# BBB_Connections.net
KiCad netlist of a schematic drawn in Altium Designer
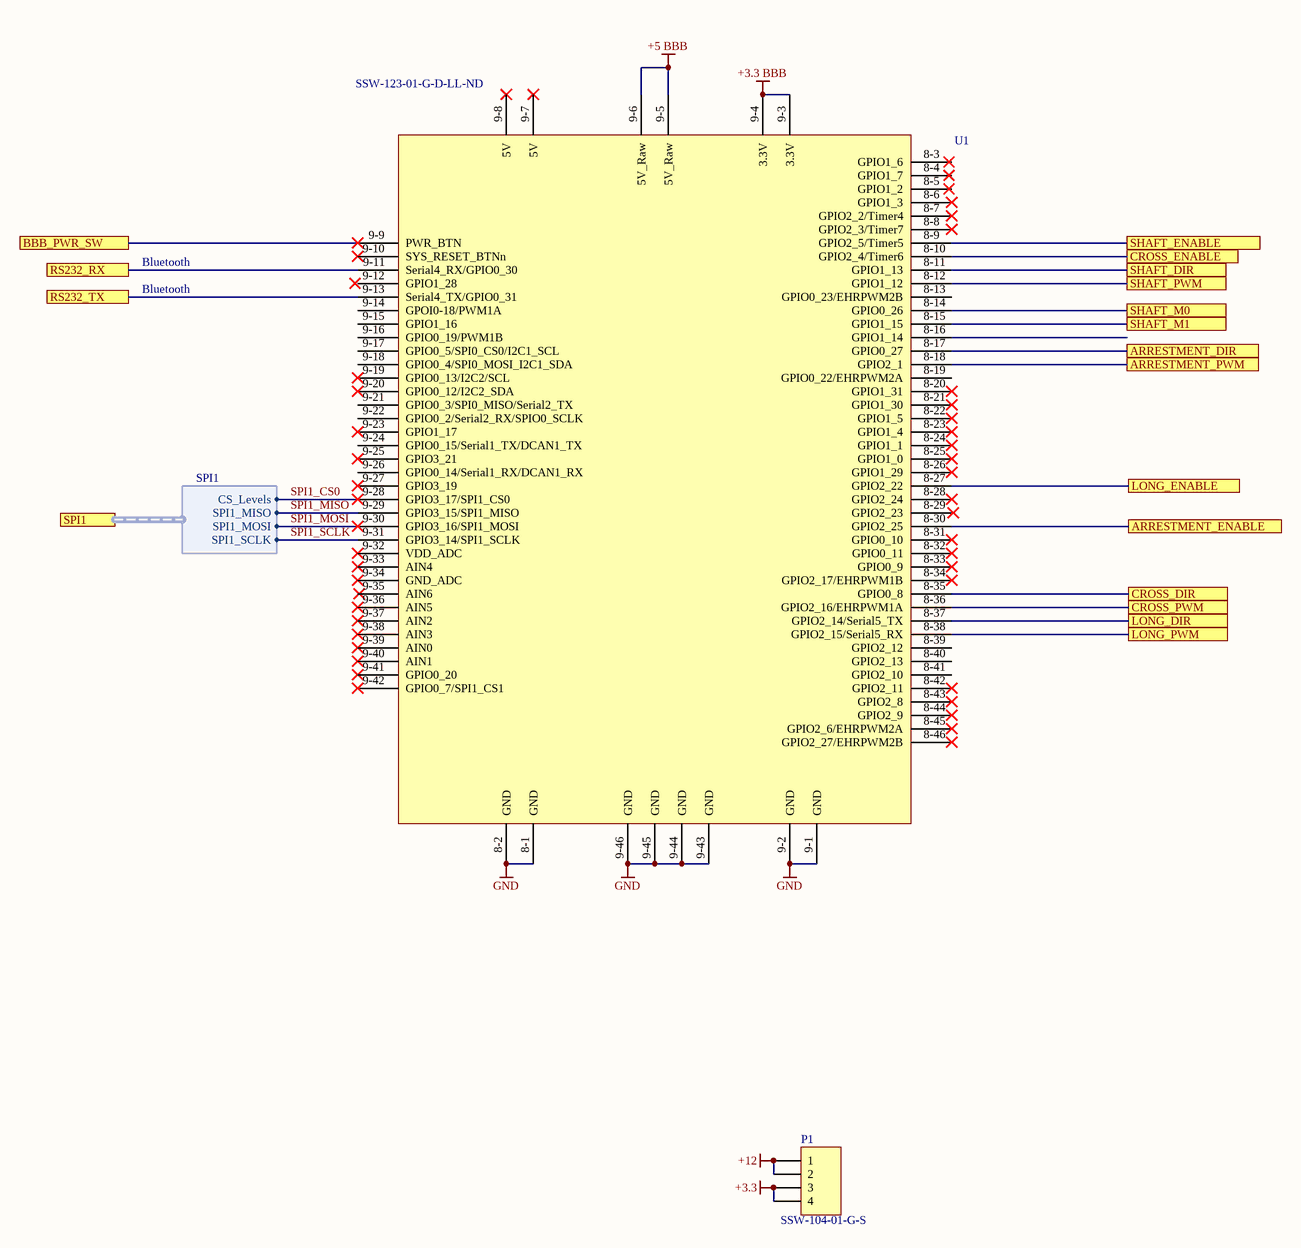
[diagram p0: BBB_Connections.SchDoc]

(export (version "E")
  (design (tool "Eeschema 10.0.6"))
  (components
    (comp (ref "P1")
      (value "SSW-104-01-G-S")
      (footprint "HDR1X4")
      (description "Header, 4-Pin")
      (fields (field (name "MANUFACTURER") "Samtec Inc."))
      (libsource (lib "Miscellaneous Connectors") (part "Header 4"))
    )
    (comp (ref "U1")
      (value "BBB")
      (footprint "Beaglebone Black Mezanine")
      (description "Beaglebone Black")
      (fields
        (field (name "SUPPLIER PART NUMBER 1") "SSW-123-01-G-D-LL-ND")
        (field (name "MANUFACTURER") "Samtec Inc.")
        (field (name "MANUFACTURER PART NUMBER") "SSW-123-01-G-D-LL")
      )
      (libsource (lib "ZLS_Schematic_lib") (part "Beaglebone_Black_Mezanine"))
    )
  )
  (nets
    (net (code "2") (name "+3.3") (class "Default")
      (node (ref "P1") (pin "3") (pinfunction "3_3") (pintype "passive"))
      (node (ref "P1") (pin "4") (pinfunction "4_4") (pintype "passive"))
    )
    (net (code "3") (name "+3.3 BBB") (class "Default")
      (node (ref "U1") (pin "9-3") (pinfunction "3.3V_9-3") (pintype "passive"))
      (node (ref "U1") (pin "9-4") (pinfunction "3.3V_9-4") (pintype "passive"))
    )
    (net (code "4") (name "+5 BBB") (class "Default")
      (node (ref "U1") (pin "9-5") (pinfunction "5V_Raw_9-5") (pintype "passive"))
      (node (ref "U1") (pin "9-6") (pinfunction "5V_Raw_9-6") (pintype "passive"))
    )
    (net (code "5") (name "+12") (class "Default")
      (node (ref "P1") (pin "1") (pinfunction "1_1") (pintype "passive"))
      (node (ref "P1") (pin "2") (pinfunction "2_2") (pintype "passive"))
    )
    (net (code "6") (name "/ARRESTMENT_DIR") (class "Default")
      (node (ref "U1") (pin "8-17") (pinfunction "GPIO0_27_8-17") (pintype "passive"))
    )
    (net (code "7") (name "/ARRESTMENT_ENABLE") (class "Default")
      (node (ref "U1") (pin "8-30") (pinfunction "GPIO2_25_8-30") (pintype "passive"))
    )
    (net (code "8") (name "/ARRESTMENT_PWM") (class "Default")
      (node (ref "U1") (pin "8-18") (pinfunction "GPIO2_1_8-18") (pintype "passive"))
    )
    (net (code "9") (name "/BBB_PWR_SW") (class "Default")
      (node (ref "U1") (pin "9-9") (pinfunction "PWR_BTN_9-9") (pintype "passive+no_connect"))
    )
    (net (code "10") (name "/CROSS_DIR") (class "Default")
      (node (ref "U1") (pin "8-35") (pinfunction "GPIO0_8_8-35") (pintype "passive"))
    )
    (net (code "11") (name "/CROSS_ENABLE") (class "Default")
      (node (ref "U1") (pin "8-10") (pinfunction "GPIO2_4/Timer6_8-10") (pintype "passive"))
    )
    (net (code "12") (name "/CROSS_PWM") (class "Default")
      (node (ref "U1") (pin "8-36") (pinfunction "GPIO2_16/EHRPWM1A_8-36") (pintype "passive"))
    )
    (net (code "13") (name "/LONG_DIR") (class "Default")
      (node (ref "U1") (pin "8-37") (pinfunction "GPIO2_14/Serial5_TX_8-37") (pintype "passive"))
    )
    (net (code "14") (name "/LONG_ENABLE") (class "Default")
      (node (ref "U1") (pin "8-27") (pinfunction "GPIO2_22_8-27") (pintype "passive"))
    )
    (net (code "15") (name "/LONG_PWM") (class "Default")
      (node (ref "U1") (pin "8-38") (pinfunction "GPIO2_15/Serial5_RX_8-38") (pintype "passive"))
    )
    (net (code "16") (name "/RS232_RX") (class "Default")
      (node (ref "U1") (pin "9-11") (pinfunction "Serial4_RX/GPIO0_30_9-11") (pintype "passive"))
    )
    (net (code "17") (name "/RS232_TX") (class "Default")
      (node (ref "U1") (pin "9-13") (pinfunction "Serial4_TX/GPIO0_31_9-13") (pintype "passive"))
    )
    (net (code "18") (name "/SHAFT_DIR") (class "Default")
      (node (ref "U1") (pin "8-11") (pinfunction "GPIO1_13_8-11") (pintype "passive"))
    )
    (net (code "19") (name "/SHAFT_ENABLE") (class "Default")
      (node (ref "U1") (pin "8-9") (pinfunction "GPIO2_5/Timer5_8-9") (pintype "passive"))
    )
    (net (code "20") (name "/SHAFT_M0") (class "Default")
      (node (ref "U1") (pin "8-14") (pinfunction "GPIO0_26_8-14") (pintype "passive"))
    )
    (net (code "21") (name "/SHAFT_M1") (class "Default")
      (node (ref "U1") (pin "8-15") (pinfunction "GPIO1_15_8-15") (pintype "passive"))
    )
    (net (code "22") (name "/SHAFT_PWM") (class "Default")
      (node (ref "U1") (pin "8-12") (pinfunction "GPIO1_12_8-12") (pintype "passive"))
    )
    (net (code "23") (name "/SPI1_CS0") (class "Default")
      (node (ref "U1") (pin "9-28") (pinfunction "GPIO3_17/SPI1_CS0_9-28") (pintype "passive+no_connect"))
    )
    (net (code "24") (name "/SPI1_MISO") (class "Default")
      (node (ref "U1") (pin "9-29") (pinfunction "GPIO3_15/SPI1_MISO_9-29") (pintype "passive"))
    )
    (net (code "25") (name "/SPI1_MOSI") (class "Default")
      (node (ref "U1") (pin "9-30") (pinfunction "GPIO3_16/SPI1_MOSI_9-30") (pintype "passive+no_connect"))
    )
    (net (code "26") (name "/SPI1_SCLK") (class "Default")
      (node (ref "U1") (pin "9-31") (pinfunction "GPIO3_14/SPI1_SCLK_9-31") (pintype "passive"))
    )
    (net (code "28") (name "GND") (class "Default")
      (node (ref "U1") (pin "8-1") (pinfunction "GND_8-1") (pintype "passive"))
      (node (ref "U1") (pin "8-2") (pinfunction "GND_8-2") (pintype "passive"))
      (node (ref "U1") (pin "9-1") (pinfunction "GND_9-1") (pintype "passive"))
      (node (ref "U1") (pin "9-2") (pinfunction "GND_9-2") (pintype "passive"))
      (node (ref "U1") (pin "9-43") (pinfunction "GND_9-43") (pintype "passive"))
      (node (ref "U1") (pin "9-44") (pinfunction "GND_9-44") (pintype "passive"))
      (node (ref "U1") (pin "9-45") (pinfunction "GND_9-45") (pintype "passive"))
      (node (ref "U1") (pin "9-46") (pinfunction "GND_9-46") (pintype "passive"))
    )
    (net (code "29") (name "unconnected-(U1-5V-Pad9-7)") (class "Default")
      (node (ref "U1") (pin "9-7") (pinfunction "5V_9-7") (pintype "passive+no_connect"))
    )
    (net (code "30") (name "unconnected-(U1-5V-Pad9-8)") (class "Default")
      (node (ref "U1") (pin "9-8") (pinfunction "5V_9-8") (pintype "passive+no_connect"))
    )
    (net (code "31") (name "unconnected-(U1-AIN0-Pad9-39)") (class "Default")
      (node (ref "U1") (pin "9-39") (pinfunction "AIN0_9-39") (pintype "passive+no_connect"))
    )
    (net (code "32") (name "unconnected-(U1-AIN1-Pad9-40)") (class "Default")
      (node (ref "U1") (pin "9-40") (pinfunction "AIN1_9-40") (pintype "passive+no_connect"))
    )
    (net (code "33") (name "unconnected-(U1-AIN2-Pad9-37)") (class "Default")
      (node (ref "U1") (pin "9-37") (pinfunction "AIN2_9-37") (pintype "passive+no_connect"))
    )
    (net (code "34") (name "unconnected-(U1-AIN3-Pad9-38)") (class "Default")
      (node (ref "U1") (pin "9-38") (pinfunction "AIN3_9-38") (pintype "passive+no_connect"))
    )
    (net (code "35") (name "unconnected-(U1-AIN4-Pad9-33)") (class "Default")
      (node (ref "U1") (pin "9-33") (pinfunction "AIN4_9-33") (pintype "passive+no_connect"))
    )
    (net (code "36") (name "unconnected-(U1-AIN5-Pad9-36)") (class "Default")
      (node (ref "U1") (pin "9-36") (pinfunction "AIN5_9-36") (pintype "passive+no_connect"))
    )
    (net (code "37") (name "unconnected-(U1-AIN6-Pad9-35)") (class "Default")
      (node (ref "U1") (pin "9-35") (pinfunction "AIN6_9-35") (pintype "passive"))
    )
    (net (code "38") (name "unconnected-(U1-GND_ADC-Pad9-34)") (class "Default")
      (node (ref "U1") (pin "9-34") (pinfunction "GND_ADC_9-34") (pintype "passive+no_connect"))
    )
    (net (code "39") (name "unconnected-(U1-GPIO0_2{slash}Serial2_RX{slash}SPIO0_SCLK-Pad9-22)") (class "Default")
      (node (ref "U1") (pin "9-22") (pinfunction "GPIO0_2/Serial2_RX/SPIO0_SCLK_9-22") (pintype "passive"))
    )
    (net (code "40") (name "unconnected-(U1-GPIO0_3{slash}SPI0_MISO{slash}Serial2_TX-Pad9-21)") (class "Default")
      (node (ref "U1") (pin "9-21") (pinfunction "GPIO0_3/SPI0_MISO/Serial2_TX_9-21") (pintype "passive"))
    )
    (net (code "41") (name "unconnected-(U1-GPIO0_4{slash}SPI0_MOSI_I2C1_SDA-Pad9-18)") (class "Default")
      (node (ref "U1") (pin "9-18") (pinfunction "GPIO0_4/SPI0_MOSI_I2C1_SDA_9-18") (pintype "passive"))
    )
    (net (code "42") (name "unconnected-(U1-GPIO0_5{slash}SPI0_CS0{slash}I2C1_SCL-Pad9-17)") (class "Default")
      (node (ref "U1") (pin "9-17") (pinfunction "GPIO0_5/SPI0_CS0/I2C1_SCL_9-17") (pintype "passive"))
    )
    (net (code "43") (name "unconnected-(U1-GPIO0_7{slash}SPI1_CS1-Pad9-42)") (class "Default")
      (node (ref "U1") (pin "9-42") (pinfunction "GPIO0_7/SPI1_CS1_9-42") (pintype "passive+no_connect"))
    )
    (net (code "44") (name "unconnected-(U1-GPIO0_9-Pad8-33)") (class "Default")
      (node (ref "U1") (pin "8-33") (pinfunction "GPIO0_9_8-33") (pintype "passive+no_connect"))
    )
    (net (code "45") (name "unconnected-(U1-GPIO0_10-Pad8-31)") (class "Default")
      (node (ref "U1") (pin "8-31") (pinfunction "GPIO0_10_8-31") (pintype "passive+no_connect"))
    )
    (net (code "46") (name "unconnected-(U1-GPIO0_11-Pad8-32)") (class "Default")
      (node (ref "U1") (pin "8-32") (pinfunction "GPIO0_11_8-32") (pintype "passive+no_connect"))
    )
    (net (code "47") (name "unconnected-(U1-GPIO0_12{slash}I2C2_SDA-Pad9-20)") (class "Default")
      (node (ref "U1") (pin "9-20") (pinfunction "GPIO0_12/I2C2_SDA_9-20") (pintype "passive+no_connect"))
    )
    (net (code "48") (name "unconnected-(U1-GPIO0_13{slash}I2C2{slash}SCL-Pad9-19)") (class "Default")
      (node (ref "U1") (pin "9-19") (pinfunction "GPIO0_13/I2C2/SCL_9-19") (pintype "passive+no_connect"))
    )
    (net (code "49") (name "unconnected-(U1-GPIO0_14{slash}Serial1_RX{slash}DCAN1_RX-Pad9-26)") (class "Default")
      (node (ref "U1") (pin "9-26") (pinfunction "GPIO0_14/Serial1_RX/DCAN1_RX_9-26") (pintype "passive"))
    )
    (net (code "50") (name "unconnected-(U1-GPIO0_15{slash}Serial1_TX{slash}DCAN1_TX-Pad9-24)") (class "Default")
      (node (ref "U1") (pin "9-24") (pinfunction "GPIO0_15/Serial1_TX/DCAN1_TX_9-24") (pintype "passive"))
    )
    (net (code "51") (name "unconnected-(U1-GPIO0_19{slash}PWM1B-Pad9-16)") (class "Default")
      (node (ref "U1") (pin "9-16") (pinfunction "GPIO0_19/PWM1B_9-16") (pintype "passive"))
    )
    (net (code "52") (name "unconnected-(U1-GPIO0_20-Pad9-41)") (class "Default")
      (node (ref "U1") (pin "9-41") (pinfunction "GPIO0_20_9-41") (pintype "passive+no_connect"))
    )
    (net (code "53") (name "unconnected-(U1-GPIO0_22{slash}EHRPWM2A-Pad8-19)") (class "Default")
      (node (ref "U1") (pin "8-19") (pinfunction "GPIO0_22/EHRPWM2A_8-19") (pintype "passive"))
    )
    (net (code "54") (name "unconnected-(U1-GPIO0_23{slash}EHRPWM2B-Pad8-13)") (class "Default")
      (node (ref "U1") (pin "8-13") (pinfunction "GPIO0_23/EHRPWM2B_8-13") (pintype "passive"))
    )
    (net (code "55") (name "unconnected-(U1-GPIO1_0-Pad8-25)") (class "Default")
      (node (ref "U1") (pin "8-25") (pinfunction "GPIO1_0_8-25") (pintype "passive+no_connect"))
    )
    (net (code "56") (name "unconnected-(U1-GPIO1_1-Pad8-24)") (class "Default")
      (node (ref "U1") (pin "8-24") (pinfunction "GPIO1_1_8-24") (pintype "passive+no_connect"))
    )
    (net (code "57") (name "unconnected-(U1-GPIO1_2-Pad8-5)") (class "Default")
      (node (ref "U1") (pin "8-5") (pinfunction "GPIO1_2_8-5") (pintype "passive"))
    )
    (net (code "58") (name "unconnected-(U1-GPIO1_3-Pad8-6)") (class "Default")
      (node (ref "U1") (pin "8-6") (pinfunction "GPIO1_3_8-6") (pintype "passive+no_connect"))
    )
    (net (code "59") (name "unconnected-(U1-GPIO1_4-Pad8-23)") (class "Default")
      (node (ref "U1") (pin "8-23") (pinfunction "GPIO1_4_8-23") (pintype "passive+no_connect"))
    )
    (net (code "60") (name "unconnected-(U1-GPIO1_5-Pad8-22)") (class "Default")
      (node (ref "U1") (pin "8-22") (pinfunction "GPIO1_5_8-22") (pintype "passive+no_connect"))
    )
    (net (code "61") (name "unconnected-(U1-GPIO1_6-Pad8-3)") (class "Default")
      (node (ref "U1") (pin "8-3") (pinfunction "GPIO1_6_8-3") (pintype "passive"))
    )
    (net (code "62") (name "unconnected-(U1-GPIO1_7-Pad8-4)") (class "Default")
      (node (ref "U1") (pin "8-4") (pinfunction "GPIO1_7_8-4") (pintype "passive"))
    )
    (net (code "63") (name "unconnected-(U1-GPIO1_14-Pad8-16)") (class "Default")
      (node (ref "U1") (pin "8-16") (pinfunction "GPIO1_14_8-16") (pintype "passive"))
    )
    (net (code "64") (name "unconnected-(U1-GPIO1_16-Pad9-15)") (class "Default")
      (node (ref "U1") (pin "9-15") (pinfunction "GPIO1_16_9-15") (pintype "passive"))
    )
    (net (code "65") (name "unconnected-(U1-GPIO1_17-Pad9-23)") (class "Default")
      (node (ref "U1") (pin "9-23") (pinfunction "GPIO1_17_9-23") (pintype "passive+no_connect"))
    )
    (net (code "66") (name "unconnected-(U1-GPIO1_28-Pad9-12)") (class "Default")
      (node (ref "U1") (pin "9-12") (pinfunction "GPIO1_28_9-12") (pintype "passive"))
    )
    (net (code "67") (name "unconnected-(U1-GPIO1_29-Pad8-26)") (class "Default")
      (node (ref "U1") (pin "8-26") (pinfunction "GPIO1_29_8-26") (pintype "passive+no_connect"))
    )
    (net (code "68") (name "unconnected-(U1-GPIO1_30-Pad8-21)") (class "Default")
      (node (ref "U1") (pin "8-21") (pinfunction "GPIO1_30_8-21") (pintype "passive+no_connect"))
    )
    (net (code "69") (name "unconnected-(U1-GPIO1_31-Pad8-20)") (class "Default")
      (node (ref "U1") (pin "8-20") (pinfunction "GPIO1_31_8-20") (pintype "passive+no_connect"))
    )
    (net (code "70") (name "unconnected-(U1-GPIO2_2{slash}Timer4-Pad8-7)") (class "Default")
      (node (ref "U1") (pin "8-7") (pinfunction "GPIO2_2/Timer4_8-7") (pintype "passive+no_connect"))
    )
    (net (code "71") (name "unconnected-(U1-GPIO2_3{slash}Timer7-Pad8-8)") (class "Default")
      (node (ref "U1") (pin "8-8") (pinfunction "GPIO2_3/Timer7_8-8") (pintype "passive+no_connect"))
    )
    (net (code "72") (name "unconnected-(U1-GPIO2_6{slash}EHRPWM2A-Pad8-45)") (class "Default")
      (node (ref "U1") (pin "8-45") (pinfunction "GPIO2_6/EHRPWM2A_8-45") (pintype "passive+no_connect"))
    )
    (net (code "73") (name "unconnected-(U1-GPIO2_8-Pad8-43)") (class "Default")
      (node (ref "U1") (pin "8-43") (pinfunction "GPIO2_8_8-43") (pintype "passive+no_connect"))
    )
    (net (code "74") (name "unconnected-(U1-GPIO2_9-Pad8-44)") (class "Default")
      (node (ref "U1") (pin "8-44") (pinfunction "GPIO2_9_8-44") (pintype "passive+no_connect"))
    )
    (net (code "75") (name "unconnected-(U1-GPIO2_10-Pad8-41)") (class "Default")
      (node (ref "U1") (pin "8-41") (pinfunction "GPIO2_10_8-41") (pintype "passive"))
    )
    (net (code "76") (name "unconnected-(U1-GPIO2_11-Pad8-42)") (class "Default")
      (node (ref "U1") (pin "8-42") (pinfunction "GPIO2_11_8-42") (pintype "passive+no_connect"))
    )
    (net (code "77") (name "unconnected-(U1-GPIO2_12-Pad8-39)") (class "Default")
      (node (ref "U1") (pin "8-39") (pinfunction "GPIO2_12_8-39") (pintype "passive"))
    )
    (net (code "78") (name "unconnected-(U1-GPIO2_13-Pad8-40)") (class "Default")
      (node (ref "U1") (pin "8-40") (pinfunction "GPIO2_13_8-40") (pintype "passive"))
    )
    (net (code "79") (name "unconnected-(U1-GPIO2_17{slash}EHRPWM1B-Pad8-34)") (class "Default")
      (node (ref "U1") (pin "8-34") (pinfunction "GPIO2_17/EHRPWM1B_8-34") (pintype "passive+no_connect"))
    )
    (net (code "80") (name "unconnected-(U1-GPIO2_23-Pad8-29)") (class "Default")
      (node (ref "U1") (pin "8-29") (pinfunction "GPIO2_23_8-29") (pintype "passive"))
    )
    (net (code "81") (name "unconnected-(U1-GPIO2_24-Pad8-28)") (class "Default")
      (node (ref "U1") (pin "8-28") (pinfunction "GPIO2_24_8-28") (pintype "passive+no_connect"))
    )
    (net (code "82") (name "unconnected-(U1-GPIO2_27{slash}EHRPWM2B-Pad8-46)") (class "Default")
      (node (ref "U1") (pin "8-46") (pinfunction "GPIO2_27/EHRPWM2B_8-46") (pintype "passive+no_connect"))
    )
    (net (code "83") (name "unconnected-(U1-GPIO3_19-Pad9-27)") (class "Default")
      (node (ref "U1") (pin "9-27") (pinfunction "GPIO3_19_9-27") (pintype "passive+no_connect"))
    )
    (net (code "84") (name "unconnected-(U1-GPIO3_21-Pad9-25)") (class "Default")
      (node (ref "U1") (pin "9-25") (pinfunction "GPIO3_21_9-25") (pintype "passive+no_connect"))
    )
    (net (code "85") (name "unconnected-(U1-GPOI0-18{slash}PWM1A-Pad9-14)") (class "Default")
      (node (ref "U1") (pin "9-14") (pinfunction "GPOI0-18/PWM1A_9-14") (pintype "passive"))
    )
    (net (code "86") (name "unconnected-(U1-SYS_RESET_BTNn-Pad9-10)") (class "Default")
      (node (ref "U1") (pin "9-10") (pinfunction "SYS_RESET_BTNn_9-10") (pintype "passive+no_connect"))
    )
    (net (code "87") (name "unconnected-(U1-VDD_ADC-Pad9-32)") (class "Default")
      (node (ref "U1") (pin "9-32") (pinfunction "VDD_ADC_9-32") (pintype "passive+no_connect"))
    )
  )
)
